# servo_distribute.net
KiCad netlist of a schematic drawn in EAGLE
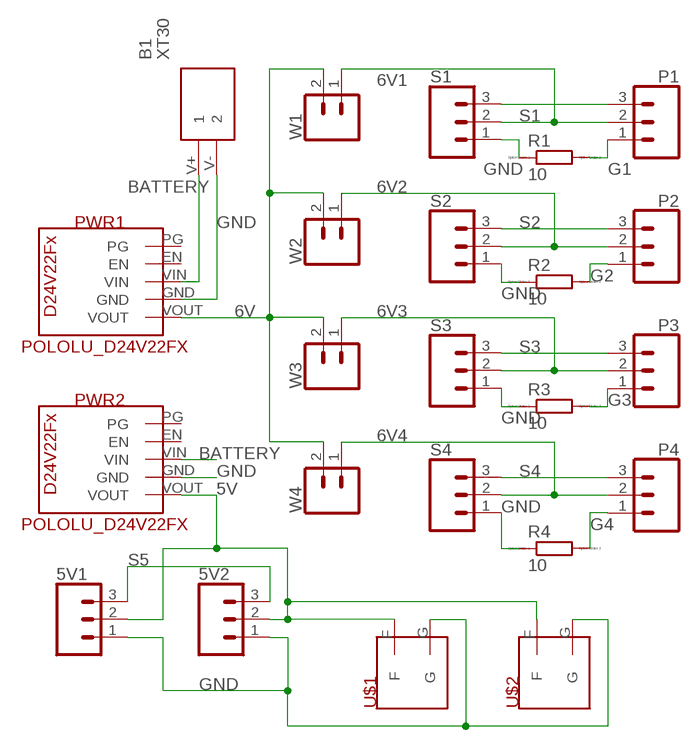
[diagram p0: schematic, sheet 1]

(export (version "E")
  (design (tool "Eeschema 10.0.6"))
  (components
    (comp (ref "5V1")
      (value "CONN_03")
      (footprint "eagle-import:1X03")
      (libsource (lib "eagle-import") (part "CONN_03"))
    )
    (comp (ref "5V2")
      (value "CONN_03")
      (footprint "eagle-import:1X03")
      (libsource (lib "eagle-import") (part "CONN_03"))
    )
    (comp (ref "B1")
      (value "XT30")
      (footprint "eagle-import:XT30PB")
      (fields (field (name "MANUFACTURER_PART_NUMBER") "XT30PB"))
      (libsource (lib "eagle-import") (part "XT30PB"))
    )
    (comp (ref "P1")
      (value "CONN_03")
      (footprint "eagle-import:1X03")
      (libsource (lib "eagle-import") (part "CONN_03"))
    )
    (comp (ref "P2")
      (value "CONN_03")
      (footprint "eagle-import:1X03")
      (libsource (lib "eagle-import") (part "CONN_03"))
    )
    (comp (ref "P3")
      (value "CONN_03")
      (footprint "eagle-import:1X03")
      (libsource (lib "eagle-import") (part "CONN_03"))
    )
    (comp (ref "P4")
      (value "CONN_03")
      (footprint "eagle-import:1X03")
      (libsource (lib "eagle-import") (part "CONN_03"))
    )
    (comp (ref "PWR1")
      (value "POLOLU_D24V22FX")
      (footprint "eagle-import:POLOLU_D24V22F6")
      (libsource (lib "eagle-import") (part "POLOLU_D24V22FX"))
    )
    (comp (ref "PWR2")
      (value "POLOLU_D24V22FX")
      (footprint "eagle-import:POLOLU_D24V22F6")
      (libsource (lib "eagle-import") (part "POLOLU_D24V22FX"))
    )
    (comp (ref "R1")
      (value "10")
      (footprint "eagle-import:R1206")
      (libsource (lib "eagle-import") (part "RR1206"))
    )
    (comp (ref "R2")
      (value "10")
      (footprint "eagle-import:R1206")
      (libsource (lib "eagle-import") (part "RR1206"))
    )
    (comp (ref "R3")
      (value "10")
      (footprint "eagle-import:R1206")
      (libsource (lib "eagle-import") (part "RR1206"))
    )
    (comp (ref "R4")
      (value "10")
      (footprint "eagle-import:R1206")
      (libsource (lib "eagle-import") (part "RR1206"))
    )
    (comp (ref "S1")
      (value "CONN_03")
      (footprint "eagle-import:1X03")
      (libsource (lib "eagle-import") (part "CONN_03"))
    )
    (comp (ref "S2")
      (value "CONN_03")
      (footprint "eagle-import:1X03")
      (libsource (lib "eagle-import") (part "CONN_03"))
    )
    (comp (ref "S3")
      (value "CONN_03")
      (footprint "eagle-import:1X03")
      (libsource (lib "eagle-import") (part "CONN_03"))
    )
    (comp (ref "S4")
      (value "CONN_03")
      (footprint "eagle-import:1X03")
      (libsource (lib "eagle-import") (part "CONN_03"))
    )
    (comp (ref "U$1")
      (value "TERMINAL_3.5MM")
      (footprint "eagle-import:TERMINAL_3.5MM")
      (libsource (lib "eagle-import") (part "TERMINAL_3.5MM"))
    )
    (comp (ref "U$2")
      (value "TERMINAL_3.5MM")
      (footprint "eagle-import:TERMINAL_3.5MM")
      (libsource (lib "eagle-import") (part "TERMINAL_3.5MM"))
    )
    (comp (ref "W1")
      (value "CONN_02")
      (footprint "eagle-import:1X02")
      (libsource (lib "eagle-import") (part "CONN_02"))
    )
    (comp (ref "W2")
      (value "CONN_02")
      (footprint "eagle-import:1X02")
      (libsource (lib "eagle-import") (part "CONN_02"))
    )
    (comp (ref "W3")
      (value "CONN_02")
      (footprint "eagle-import:1X02")
      (libsource (lib "eagle-import") (part "CONN_02"))
    )
    (comp (ref "W4")
      (value "CONN_02")
      (footprint "eagle-import:1X02")
      (libsource (lib "eagle-import") (part "CONN_02"))
    )
  )
  (nets
    (net (code "1") (name "/5V") (class "Default")
      (node (ref "5V1") (pin "2") (pinfunction "2_2") (pintype "passive"))
      (node (ref "5V2") (pin "2") (pinfunction "2_2") (pintype "passive"))
      (node (ref "PWR2") (pin "VOUT") (pinfunction "VOUT_VOUT") (pintype "bidirectional"))
      (node (ref "U$1") (pin "F") (pinfunction "F_F") (pintype "bidirectional"))
      (node (ref "U$2") (pin "F") (pinfunction "F_F") (pintype "bidirectional"))
    )
    (net (code "2") (name "/6V") (class "Default")
      (node (ref "PWR1") (pin "VOUT") (pinfunction "VOUT_VOUT") (pintype "bidirectional"))
      (node (ref "W1") (pin "2") (pinfunction "2_2") (pintype "passive"))
      (node (ref "W2") (pin "2") (pinfunction "2_2") (pintype "passive"))
      (node (ref "W3") (pin "2") (pinfunction "2_2") (pintype "passive"))
      (node (ref "W4") (pin "2") (pinfunction "2_2") (pintype "passive"))
    )
    (net (code "3") (name "/6V1") (class "Default")
      (node (ref "P1") (pin "2") (pinfunction "2_2") (pintype "passive"))
      (node (ref "S1") (pin "2") (pinfunction "2_2") (pintype "passive"))
      (node (ref "W1") (pin "1") (pinfunction "1_1") (pintype "passive"))
    )
    (net (code "4") (name "/6V2") (class "Default")
      (node (ref "P2") (pin "2") (pinfunction "2_2") (pintype "passive"))
      (node (ref "S2") (pin "2") (pinfunction "2_2") (pintype "passive"))
      (node (ref "W2") (pin "1") (pinfunction "1_1") (pintype "passive"))
    )
    (net (code "5") (name "/6V3") (class "Default")
      (node (ref "P3") (pin "2") (pinfunction "2_2") (pintype "passive"))
      (node (ref "S3") (pin "2") (pinfunction "2_2") (pintype "passive"))
      (node (ref "W3") (pin "1") (pinfunction "1_1") (pintype "passive"))
    )
    (net (code "6") (name "/6V4") (class "Default")
      (node (ref "P4") (pin "2") (pinfunction "2_2") (pintype "passive"))
      (node (ref "S4") (pin "2") (pinfunction "2_2") (pintype "passive"))
      (node (ref "W4") (pin "1") (pinfunction "1_1") (pintype "passive"))
    )
    (net (code "7") (name "/BATTERY") (class "Default")
      (node (ref "B1") (pin "V+") (pinfunction "1_V+") (pintype "bidirectional"))
      (node (ref "PWR1") (pin "VIN") (pinfunction "VIN_VIN") (pintype "bidirectional"))
      (node (ref "PWR2") (pin "VIN") (pinfunction "VIN_VIN") (pintype "bidirectional"))
    )
    (net (code "8") (name "/G1") (class "Default")
      (node (ref "P1") (pin "1") (pinfunction "1_1") (pintype "passive"))
      (node (ref "R1") (pin "2") (pinfunction "2_2") (pintype "passive"))
    )
    (net (code "9") (name "/G2") (class "Default")
      (node (ref "P2") (pin "1") (pinfunction "1_1") (pintype "passive"))
      (node (ref "R2") (pin "2") (pinfunction "2_2") (pintype "passive"))
    )
    (net (code "10") (name "/G3") (class "Default")
      (node (ref "P3") (pin "1") (pinfunction "1_1") (pintype "passive"))
      (node (ref "R3") (pin "2") (pinfunction "2_2") (pintype "passive"))
    )
    (net (code "11") (name "/G4") (class "Default")
      (node (ref "P4") (pin "1") (pinfunction "1_1") (pintype "passive"))
      (node (ref "R4") (pin "2") (pinfunction "2_2") (pintype "passive"))
    )
    (net (code "12") (name "/GND") (class "Default")
      (node (ref "5V1") (pin "1") (pinfunction "1_1") (pintype "passive"))
      (node (ref "5V2") (pin "1") (pinfunction "1_1") (pintype "passive"))
      (node (ref "B1") (pin "V-") (pinfunction "2_V-") (pintype "bidirectional"))
      (node (ref "PWR1") (pin "GND") (pinfunction "GND_GND") (pintype "bidirectional"))
      (node (ref "PWR2") (pin "GND") (pinfunction "GND_GND") (pintype "bidirectional"))
      (node (ref "R1") (pin "1") (pinfunction "1_1") (pintype "passive"))
      (node (ref "R2") (pin "1") (pinfunction "1_1") (pintype "passive"))
      (node (ref "R3") (pin "1") (pinfunction "1_1") (pintype "passive"))
      (node (ref "R4") (pin "1") (pinfunction "1_1") (pintype "passive"))
      (node (ref "S1") (pin "1") (pinfunction "1_1") (pintype "passive"))
      (node (ref "S2") (pin "1") (pinfunction "1_1") (pintype "passive"))
      (node (ref "S3") (pin "1") (pinfunction "1_1") (pintype "passive"))
      (node (ref "S4") (pin "1") (pinfunction "1_1") (pintype "passive"))
      (node (ref "U$1") (pin "G") (pinfunction "G_G") (pintype "bidirectional"))
      (node (ref "U$2") (pin "G") (pinfunction "G_G") (pintype "bidirectional"))
    )
    (net (code "13") (name "/S1") (class "Default")
      (node (ref "P1") (pin "3") (pinfunction "3_3") (pintype "passive"))
      (node (ref "S1") (pin "3") (pinfunction "3_3") (pintype "passive"))
    )
    (net (code "14") (name "/S2") (class "Default")
      (node (ref "P2") (pin "3") (pinfunction "3_3") (pintype "passive"))
      (node (ref "S2") (pin "3") (pinfunction "3_3") (pintype "passive"))
    )
    (net (code "15") (name "/S3") (class "Default")
      (node (ref "P3") (pin "3") (pinfunction "3_3") (pintype "passive"))
      (node (ref "S3") (pin "3") (pinfunction "3_3") (pintype "passive"))
    )
    (net (code "16") (name "/S4") (class "Default")
      (node (ref "P4") (pin "3") (pinfunction "3_3") (pintype "passive"))
      (node (ref "S4") (pin "3") (pinfunction "3_3") (pintype "passive"))
    )
    (net (code "17") (name "/S5") (class "Default")
      (node (ref "5V1") (pin "3") (pinfunction "3_3") (pintype "passive"))
      (node (ref "5V2") (pin "3") (pinfunction "3_3") (pintype "passive"))
    )
    (net (code "18") (name "unconnected-(PWR1-PadEN)") (class "Default")
      (node (ref "PWR1") (pin "EN") (pinfunction "EN_EN") (pintype "bidirectional"))
    )
    (net (code "19") (name "unconnected-(PWR1-PadPG)") (class "Default")
      (node (ref "PWR1") (pin "PG") (pinfunction "PG_PG") (pintype "bidirectional"))
    )
    (net (code "20") (name "unconnected-(PWR2-PadEN)") (class "Default")
      (node (ref "PWR2") (pin "EN") (pinfunction "EN_EN") (pintype "bidirectional"))
    )
    (net (code "21") (name "unconnected-(PWR2-PadPG)") (class "Default")
      (node (ref "PWR2") (pin "PG") (pinfunction "PG_PG") (pintype "bidirectional"))
    )
  )
)
